# ShifterBit2.net
KiCad netlist of a schematic drawn in EAGLE
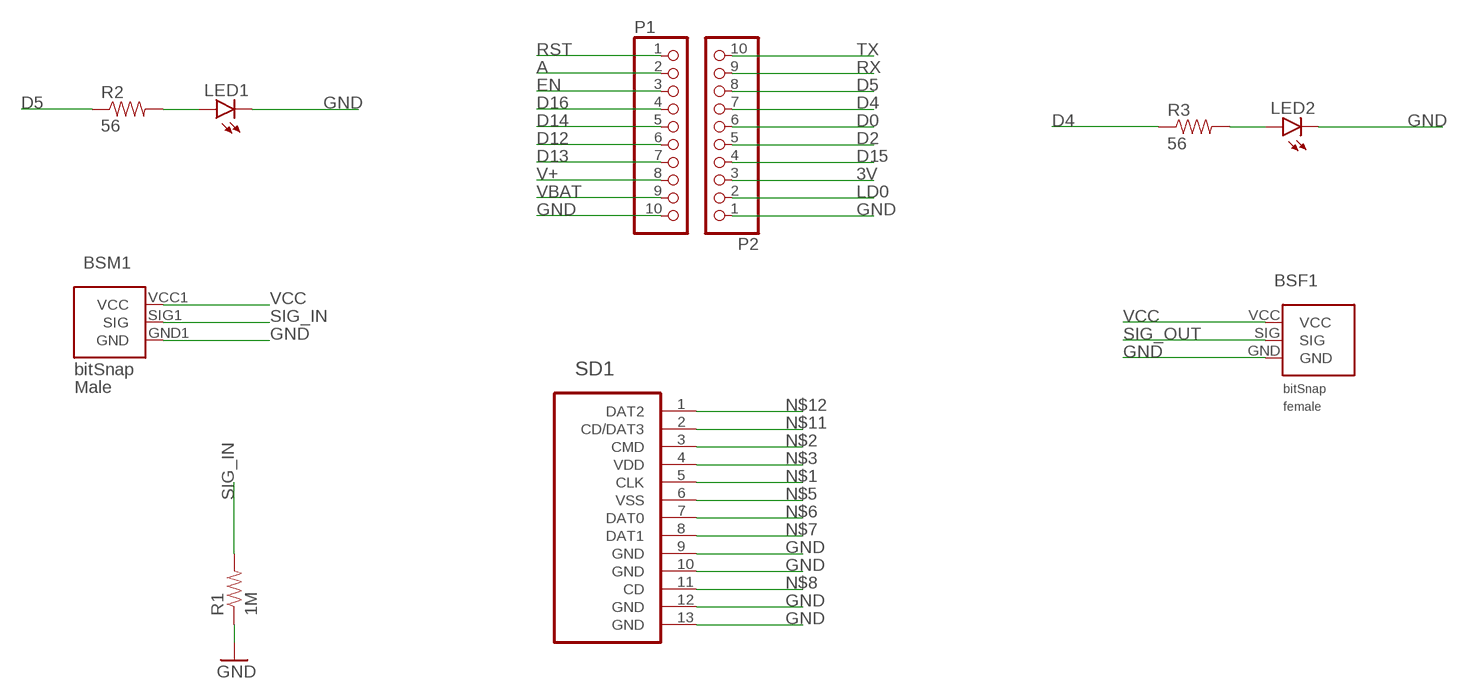
[diagram p0: schematic, sheet 1]

(export (version "E")
  (design (tool "Eeschema 10.0.6"))
  (components
    (comp (ref "BSF1")
      (value "BITSNAP_V03_FEMALE")
      (footprint "eagle-import:BITSNAP_V03_FEMALE")
      (libsource (lib "eagle-import") (part "BITSNAP_V03_FEMALE"))
    )
    (comp (ref "BSM1")
      (value "BITSNAP_V03_MALE")
      (footprint "eagle-import:BITSNAP_V03_MALE")
      (libsource (lib "eagle-import") (part "BITSNAP_V03_MALE"))
    )
    (comp (ref "LED1")
      (value "LED-GREEN0603")
      (footprint "eagle-import:LED-0603")
      (libsource (lib "eagle-import") (part "LED-GREEN0603"))
    )
    (comp (ref "LED2")
      (value "LED-GREEN0603")
      (footprint "eagle-import:LED-0603")
      (libsource (lib "eagle-import") (part "LED-GREEN0603"))
    )
    (comp (ref "P1")
      (value "PINHD-1X10")
      (footprint "eagle-import:1X10-BIG")
      (libsource (lib "eagle-import") (part "PINHD-1X10"))
    )
    (comp (ref "P2")
      (value "PINHD-1X10")
      (footprint "eagle-import:1X10-BIG")
      (libsource (lib "eagle-import") (part "PINHD-1X10"))
    )
    (comp (ref "R1")
      (value "1M")
      (footprint "eagle-import:RES-0603")
      (libsource (lib "eagle-import") (part "RESISTOR0603"))
    )
    (comp (ref "R2")
      (value "56")
      (footprint "eagle-import:0603-RES")
      (libsource (lib "eagle-import") (part "RESISTOR0603-RES"))
    )
    (comp (ref "R3")
      (value "56")
      (footprint "eagle-import:0603-RES")
      (libsource (lib "eagle-import") (part "RESISTOR0603-RES"))
    )
    (comp (ref "SD1")
      (value "HIROSE_DM3CS-SF")
      (footprint "eagle-import:HIROSE_DM3CS-SF")
      (fields (field (name "MPN") "DM3CS-SF"))
      (libsource (lib "eagle-import") (part "HIROSE_DM3CS-SF"))
    )
  )
  (nets
    (net (code "1") (name "/3V") (class "Default")
      (node (ref "P2") (pin "3") (pinfunction "3_3") (pintype "passive"))
    )
    (net (code "2") (name "/A") (class "Default")
      (node (ref "P1") (pin "2") (pinfunction "2_2") (pintype "passive"))
    )
    (net (code "3") (name "/D0") (class "Default")
      (node (ref "P2") (pin "6") (pinfunction "6_6") (pintype "passive"))
    )
    (net (code "4") (name "/D2") (class "Default")
      (node (ref "P2") (pin "5") (pinfunction "5_5") (pintype "passive"))
    )
    (net (code "5") (name "/D4") (class "Default")
      (node (ref "P2") (pin "7") (pinfunction "7_7") (pintype "passive"))
      (node (ref "R3") (pin "1") (pinfunction "1_1") (pintype "passive"))
    )
    (net (code "6") (name "/D5") (class "Default")
      (node (ref "P2") (pin "8") (pinfunction "8_8") (pintype "passive"))
      (node (ref "R2") (pin "1") (pinfunction "1_1") (pintype "passive"))
    )
    (net (code "7") (name "/D12") (class "Default")
      (node (ref "P1") (pin "6") (pinfunction "6_6") (pintype "passive"))
    )
    (net (code "8") (name "/D13") (class "Default")
      (node (ref "P1") (pin "7") (pinfunction "7_7") (pintype "passive"))
    )
    (net (code "9") (name "/D14") (class "Default")
      (node (ref "P1") (pin "5") (pinfunction "5_5") (pintype "passive"))
    )
    (net (code "10") (name "/D15") (class "Default")
      (node (ref "P2") (pin "4") (pinfunction "4_4") (pintype "passive"))
    )
    (net (code "11") (name "/D16") (class "Default")
      (node (ref "P1") (pin "4") (pinfunction "4_4") (pintype "passive"))
    )
    (net (code "12") (name "/EN") (class "Default")
      (node (ref "P1") (pin "3") (pinfunction "3_3") (pintype "passive"))
    )
    (net (code "13") (name "/LD0") (class "Default")
      (node (ref "P2") (pin "2") (pinfunction "2_2") (pintype "passive"))
    )
    (net (code "14") (name "/N$1") (class "Default")
      (node (ref "SD1") (pin "5") (pinfunction "CLK_5") (pintype "passive"))
    )
    (net (code "15") (name "/N$2") (class "Default")
      (node (ref "SD1") (pin "3") (pinfunction "CMD_3") (pintype "passive"))
    )
    (net (code "16") (name "/N$3") (class "Default")
      (node (ref "SD1") (pin "4") (pinfunction "VDD_4") (pintype "passive"))
    )
    (net (code "17") (name "/N$5") (class "Default")
      (node (ref "SD1") (pin "6") (pinfunction "VSS_6") (pintype "passive"))
    )
    (net (code "18") (name "/N$6") (class "Default")
      (node (ref "SD1") (pin "7") (pinfunction "DAT0_7") (pintype "passive"))
    )
    (net (code "19") (name "/N$7") (class "Default")
      (node (ref "SD1") (pin "8") (pinfunction "DAT1_8") (pintype "passive"))
    )
    (net (code "20") (name "/N$8") (class "Default")
      (node (ref "SD1") (pin "11") (pinfunction "CD_11") (pintype "passive"))
    )
    (net (code "21") (name "/N$11") (class "Default")
      (node (ref "SD1") (pin "2") (pinfunction "CD/DAT3_2") (pintype "passive"))
    )
    (net (code "22") (name "/N$12") (class "Default")
      (node (ref "SD1") (pin "1") (pinfunction "DAT2_1") (pintype "passive"))
    )
    (net (code "23") (name "/RST") (class "Default")
      (node (ref "P1") (pin "1") (pinfunction "1_1") (pintype "passive"))
    )
    (net (code "24") (name "/RX") (class "Default")
      (node (ref "P2") (pin "9") (pinfunction "9_9") (pintype "passive"))
    )
    (net (code "25") (name "/SIG_IN") (class "Default")
      (node (ref "BSM1") (pin "SIG1") (pinfunction "SIG_SIG1") (pintype "bidirectional"))
      (node (ref "R1") (pin "2") (pinfunction "2_2") (pintype "passive"))
    )
    (net (code "26") (name "/SIG_OUT") (class "Default")
      (node (ref "BSF1") (pin "SIG") (pinfunction "SIG_SIG") (pintype "bidirectional"))
    )
    (net (code "27") (name "/TX") (class "Default")
      (node (ref "P2") (pin "10") (pinfunction "10_10") (pintype "passive"))
    )
    (net (code "28") (name "/V+") (class "Default")
      (node (ref "P1") (pin "8") (pinfunction "8_8") (pintype "passive"))
    )
    (net (code "29") (name "/VBAT") (class "Default")
      (node (ref "P1") (pin "9") (pinfunction "9_9") (pintype "passive"))
    )
    (net (code "30") (name "/VCC") (class "Default")
      (node (ref "BSF1") (pin "VCC") (pinfunction "VCC_VCC") (pintype "bidirectional"))
      (node (ref "BSM1") (pin "VCC1") (pinfunction "VCC_VCC1") (pintype "bidirectional"))
    )
    (net (code "31") (name "GND") (class "Default")
      (node (ref "BSF1") (pin "GND") (pinfunction "GND_GND") (pintype "bidirectional"))
      (node (ref "BSM1") (pin "GND1") (pinfunction "GND_GND1") (pintype "bidirectional"))
      (node (ref "LED1") (pin "C") (pinfunction "C_C") (pintype "passive"))
      (node (ref "LED2") (pin "C") (pinfunction "C_C") (pintype "passive"))
      (node (ref "P1") (pin "10") (pinfunction "10_10") (pintype "passive"))
      (node (ref "P2") (pin "1") (pinfunction "1_1") (pintype "passive"))
      (node (ref "R1") (pin "1") (pinfunction "1_1") (pintype "passive"))
      (node (ref "SD1") (pin "10") (pinfunction "GND_10") (pintype "passive"))
      (node (ref "SD1") (pin "12") (pinfunction "GND_12") (pintype "passive"))
      (node (ref "SD1") (pin "13") (pinfunction "GND_13") (pintype "passive"))
      (node (ref "SD1") (pin "9") (pinfunction "GND_9") (pintype "passive"))
    )
    (net (code "32") (name "Net-(LED1-PadA)") (class "Default")
      (node (ref "LED1") (pin "A") (pinfunction "A_A") (pintype "passive"))
      (node (ref "R2") (pin "2") (pinfunction "2_2") (pintype "passive"))
    )
    (net (code "33") (name "Net-(LED2-PadA)") (class "Default")
      (node (ref "LED2") (pin "A") (pinfunction "A_A") (pintype "passive"))
      (node (ref "R3") (pin "2") (pinfunction "2_2") (pintype "passive"))
    )
  )
)
